# SimulatorT2GenericSensorRevC.net
KiCad netlist of a schematic drawn in EAGLE
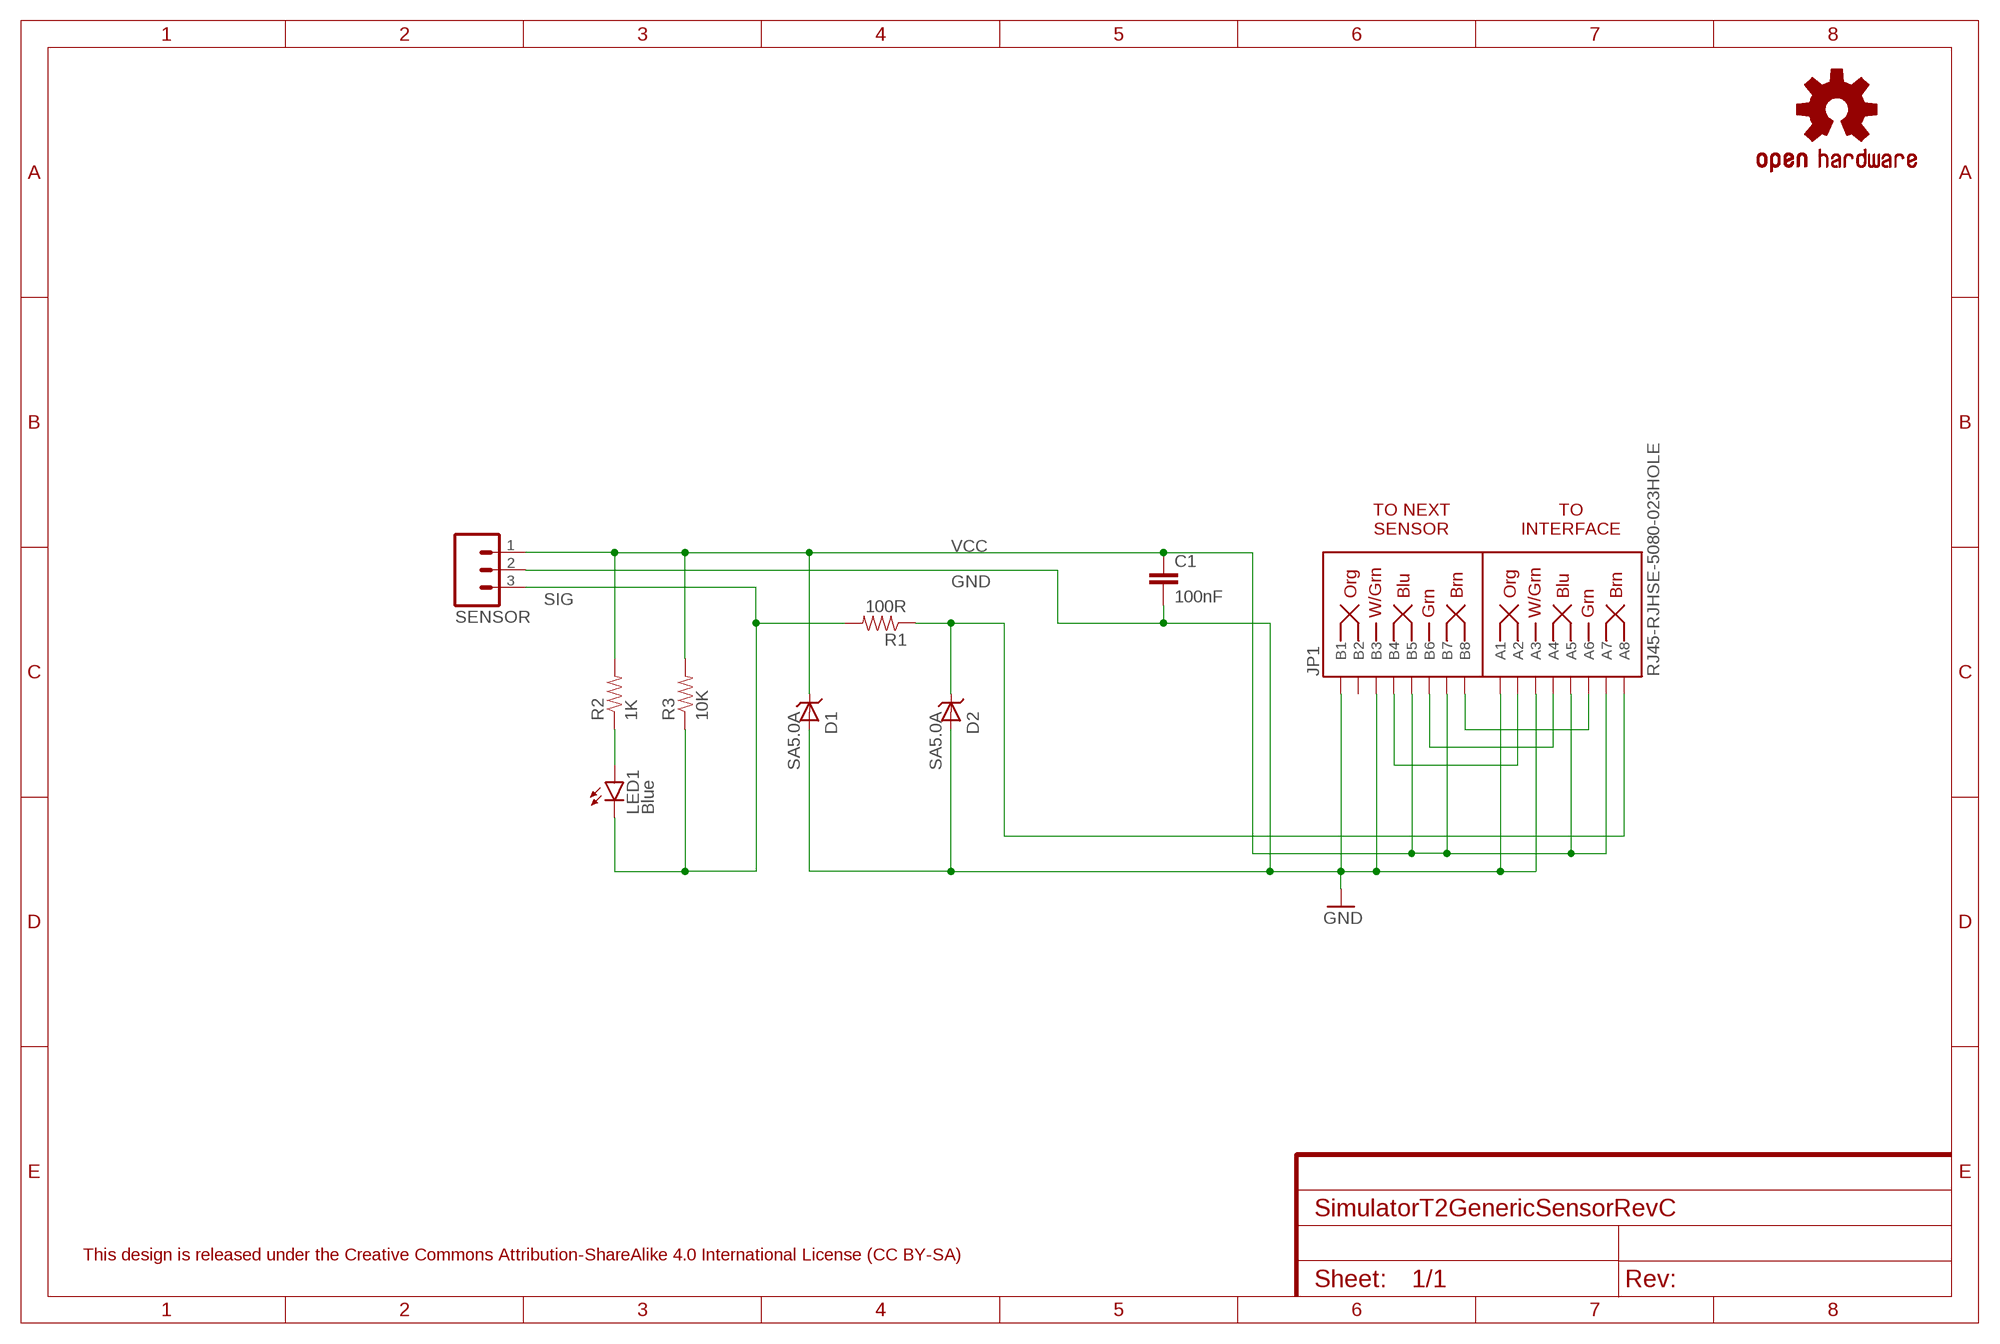
[diagram p0: schematic, sheet 1]

(export (version "E")
  (design (tool "Eeschema 10.0.6"))
  (components
    (comp (ref "C1")
      (value "100nF")
      (footprint "eagle-import:CAP-PTH-SMALL")
      (libsource (lib "eagle-import") (part "CAPPTH"))
    )
    (comp (ref "D1")
      (value "SA5.0A")
      (footprint "eagle-import:DO41_TVS_UNI")
      (libsource (lib "eagle-import") (part "SA5.0A"))
    )
    (comp (ref "D2")
      (value "SA5.0A")
      (footprint "eagle-import:DO41_TVS_UNI")
      (libsource (lib "eagle-import") (part "SA5.0A"))
    )
    (comp (ref "JP1")
      (value "RJ45-RJHSE-5080-023HOLE")
      (footprint "eagle-import:RJ45-RJHSE-5080-02-3HOLE")
      (libsource (lib "eagle-import") (part "RJ45-RJHSE-5080-023HOLE"))
    )
    (comp (ref "LED1")
      (value "Blue")
      (footprint "eagle-import:LED3MM")
      (libsource (lib "eagle-import") (part "LED3MM"))
    )
    (comp (ref "LOGO1")
      (value "OSHW-LOGOS")
      (footprint "eagle-import:OSHW-LOGO-S")
      (libsource (lib "eagle-import") (part "OSHW-LOGOS"))
    )
    (comp (ref "R1")
      (value "100R")
      (footprint "eagle-import:AXIAL-0.4")
      (libsource (lib "eagle-import") (part "RESISTORPTH-1/4W"))
    )
    (comp (ref "R2")
      (value "1K")
      (footprint "eagle-import:AXIAL-0.4")
      (libsource (lib "eagle-import") (part "RESISTORPTH-1/4W"))
    )
    (comp (ref "R3")
      (value "10K")
      (footprint "eagle-import:AXIAL-0.4")
      (libsource (lib "eagle-import") (part "RESISTORPTH-1/4W"))
    )
    (comp (ref "SENSOR")
      (value "M03PTH")
      (footprint "eagle-import:1X03")
      (libsource (lib "eagle-import") (part "M03PTH"))
    )
  )
  (nets
    (net (code "1") (name "/SIG") (class "Default")
      (node (ref "LED1") (pin "K") (pinfunction "C_K") (pintype "passive"))
      (node (ref "R1") (pin "P$2") (pinfunction "2_P$2") (pintype "passive"))
      (node (ref "R3") (pin "P$1") (pinfunction "1_P$1") (pintype "passive"))
      (node (ref "SENSOR") (pin "3") (pinfunction "3_3") (pintype "passive"))
    )
    (net (code "2") (name "/VCC") (class "Default")
      (node (ref "C1") (pin "1") (pinfunction "1_1") (pintype "passive"))
      (node (ref "D1") (pin "CATHODE") (pinfunction "CATHODE_CATHODE") (pintype "passive"))
      (node (ref "JP1") (pin "A5") (pinfunction "A5_A5") (pintype "bidirectional"))
      (node (ref "JP1") (pin "A7") (pinfunction "A7_A7") (pintype "bidirectional"))
      (node (ref "JP1") (pin "B5") (pinfunction "B5_B5") (pintype "bidirectional"))
      (node (ref "JP1") (pin "B7") (pinfunction "B7_B7") (pintype "bidirectional"))
      (node (ref "R2") (pin "P$2") (pinfunction "2_P$2") (pintype "passive"))
      (node (ref "R3") (pin "P$2") (pinfunction "2_P$2") (pintype "passive"))
      (node (ref "SENSOR") (pin "1") (pinfunction "1_1") (pintype "passive"))
    )
    (net (code "3") (name "GND") (class "Default")
      (node (ref "C1") (pin "2") (pinfunction "2_2") (pintype "passive"))
      (node (ref "D1") (pin "ANODE") (pinfunction "ANODE_ANODE") (pintype "passive"))
      (node (ref "D2") (pin "ANODE") (pinfunction "ANODE_ANODE") (pintype "passive"))
      (node (ref "JP1") (pin "A1") (pinfunction "A1_A1") (pintype "bidirectional"))
      (node (ref "JP1") (pin "A3") (pinfunction "A3_A3") (pintype "bidirectional"))
      (node (ref "JP1") (pin "B1") (pinfunction "B1_B1") (pintype "bidirectional"))
      (node (ref "JP1") (pin "B3") (pinfunction "B3_B3") (pintype "bidirectional"))
      (node (ref "SENSOR") (pin "2") (pinfunction "2_2") (pintype "passive"))
    )
    (net (code "4") (name "Net-(JP1-PadA2)") (class "Default")
      (node (ref "JP1") (pin "A2") (pinfunction "A2_A2") (pintype "bidirectional"))
      (node (ref "JP1") (pin "B4") (pinfunction "B4_B4") (pintype "bidirectional"))
    )
    (net (code "5") (name "Net-(JP1-PadA4)") (class "Default")
      (node (ref "JP1") (pin "A4") (pinfunction "A4_A4") (pintype "bidirectional"))
      (node (ref "JP1") (pin "B6") (pinfunction "B6_B6") (pintype "bidirectional"))
    )
    (net (code "6") (name "Net-(JP1-PadA6)") (class "Default")
      (node (ref "JP1") (pin "A6") (pinfunction "A6_A6") (pintype "bidirectional"))
      (node (ref "JP1") (pin "B8") (pinfunction "B8_B8") (pintype "bidirectional"))
    )
    (net (code "7") (name "Net-(R1-1)") (class "Default")
      (node (ref "D2") (pin "CATHODE") (pinfunction "CATHODE_CATHODE") (pintype "passive"))
      (node (ref "JP1") (pin "A8") (pinfunction "A8_A8") (pintype "bidirectional"))
      (node (ref "R1") (pin "P$1") (pinfunction "1_P$1") (pintype "passive"))
    )
    (net (code "8") (name "Net-(R2-1)") (class "Default")
      (node (ref "LED1") (pin "A") (pinfunction "A_A") (pintype "passive"))
      (node (ref "R2") (pin "P$1") (pinfunction "1_P$1") (pintype "passive"))
    )
    (net (code "9") (name "unconnected-(JP1-PadB2)") (class "Default")
      (node (ref "JP1") (pin "B2") (pinfunction "B2_B2") (pintype "bidirectional"))
    )
  )
)
